# 02_CAN.net
KiCad netlist of a schematic drawn in Altium Designer
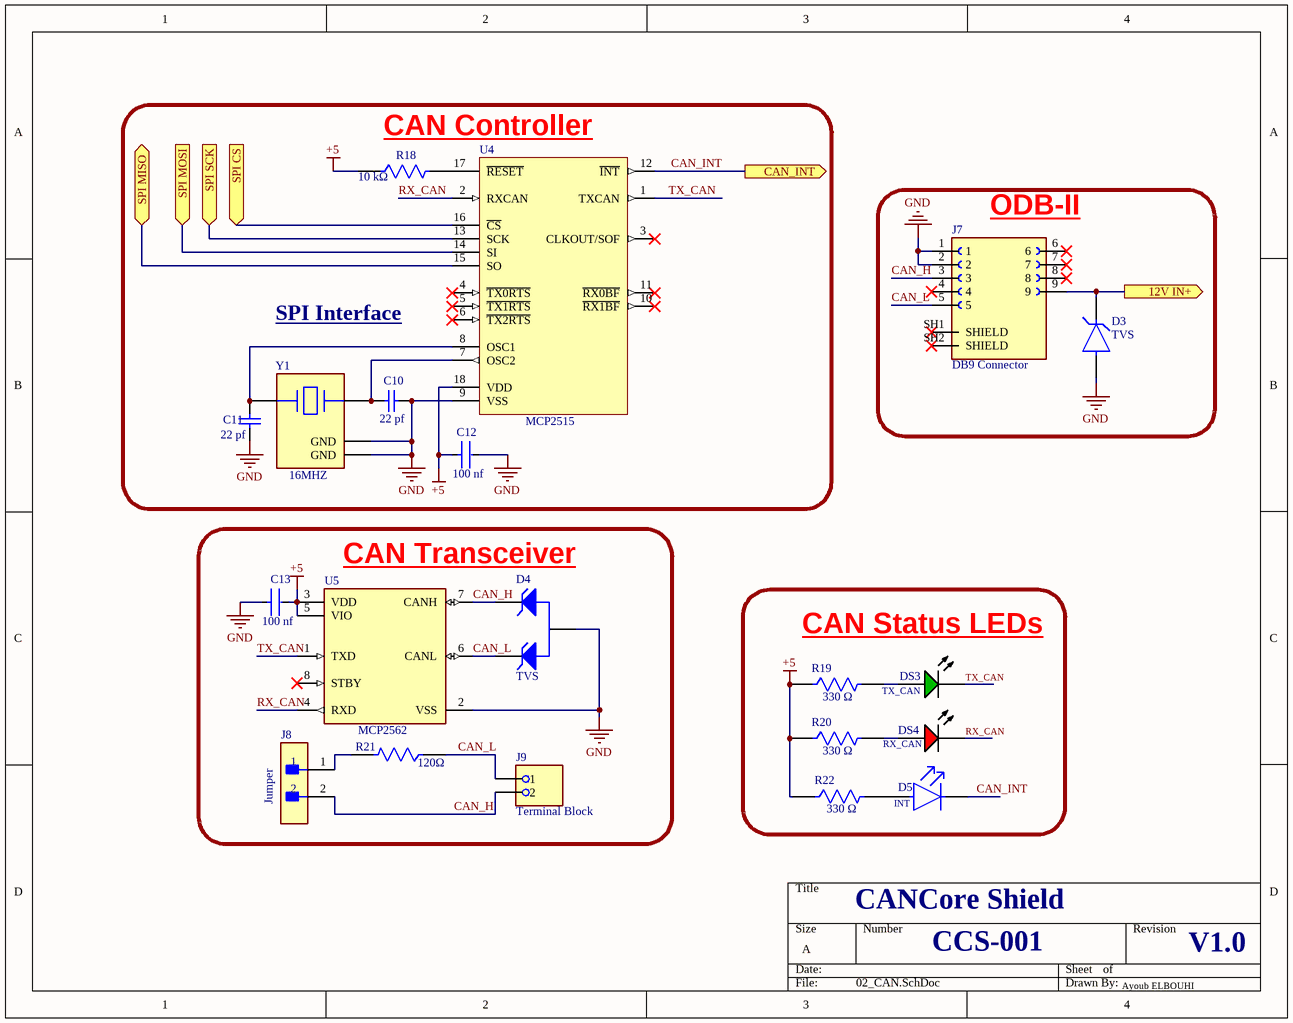
[diagram p0: 02_CAN.SchDoc]

(export (version "E")
  (design (tool "Eeschema 10.0.6"))
  (components
    (comp (ref "C10")
      (value "22 pf")
      (footprint "CAPC1608X90X35ML15T15")
      (fields
        (field (name "MANUFACTURER") "AVX Interconnect / Elco")
        (field (name "PART NUMBER") "06035A220KAT2A")
      )
      (libsource (lib "Altium Content Vault") (part "CAP"))
    )
    (comp (ref "C11")
      (value "22 pf")
      (footprint "CAPC1608X90X35ML15T15")
      (fields
        (field (name "MANUFACTURER") "AVX Interconnect / Elco")
        (field (name "PART NUMBER") "06035A220KAT2A")
      )
      (libsource (lib "Altium Content Vault") (part "CAP"))
    )
    (comp (ref "C12")
      (value "100 nf")
      (footprint "FP-0204-L_0_52_0_05-W_1_0-IPC_B")
      (description "None")
      (fields (field (name "TOLERANCE") "20%"))
      (libsource (lib "Altium Content Vault") (part "b4654b650e69147ec39a6b967a45e02"))
    )
    (comp (ref "C13")
      (value "100 nf")
      (footprint "FP-0204-L_0_52_0_05-W_1_0-IPC_B")
      (description "None")
      (fields (field (name "TOLERANCE") "20%"))
      (libsource (lib "Altium Content Vault") (part "b4654b650e69147ec39a6b967a45e02"))
    )
    (comp (ref "D3")
      (value "TVS")
      (footprint "FP-SMBJ-MFG")
      (description "TVS DIODE 24V 38.9V SMB")
      (libsource (lib "Altium Content Vault") (part "f813f71cba58e380607f5dd3caf9714"))
    )
    (comp (ref "D4")
      (value "TVS")
      (footprint "JSCJ-SOT23-3_V")
      (description "Uni-direction ESD Protection Diode, 5 V, 10 uA, 3-Pin SOT23, RoHS, Tape and Reel")
      (fields (field (name "MANUFACTURER") "Jiangsu Changjiang Electronics Technology"))
      (libsource (lib "Altium Content Vault") (part "DZEN-KKA-3"))
    )
    (comp (ref "D5")
      (value "INT")
      (footprint "FP-LTST-C170TBKT-MFG")
      (description "LED BLUE CLEAR SMD")
      (libsource (lib "Altium Content Vault") (part "8706943c75ba83719d021d2fdc84c58"))
    )
    (comp (ref "DS3")
      (value "TX_CAN")
      (footprint "LTST-LTST-C170KGKT-2_V")
      (description "Ultra Bright AlInGaP Chip LED, 75 mW, -55 to 85 degC, 2-Pin SMD (0805), RoHS, Tape and Reel")
      (fields (field (name "MANUFACTURER") "Lite-On"))
      (libsource (lib "Altium Content Vault") (part "LED-GREEN-KA-2"))
    )
    (comp (ref "DS4")
      (value "RX_CAN")
      (footprint "LTST-C170KRKT_V")
      (description "LED Red, 75 mW, 54 mcd, -55 to 85 degC, 2-Pin SMD, RoHS, Tape and Reel")
      (fields (field (name "MANUFACTURER") "Lite-On"))
      (libsource (lib "Altium Content Vault") (part "LED-RED-AK-2"))
    )
    (comp (ref "J7")
      (value "DB9 Connector")
      (footprint "AMPHENOL_L77SDE09SA4CH4F48")
      (fields
        (field (name "MF") "Amphenol ICC (Commercial Products)")
        (field (name "MP") "L77SDE09SA4CH4F48")
      )
      (libsource (lib "L77SDE09SA4CH4F48") (part "L77SDE09SA4CH4F48"))
    )
    (comp (ref "J8")
      (value "Jumper")
      (footprint "FP-TSW-102-07-G-S-MFG")
      (description "CONN HEADER VERT 2POS 2.54MM")
      (fields
        (field (name "MANUFACTURER") "Samtec")
        (field (name "MANUFACTURER PART NUMBER") "TSW-102-07-G-S")
      )
      (libsource (lib "Altium Content Vault") (part "3bc925449376181038e59eaffc5286c"))
    )
    (comp (ref "J9")
      (value "Terminal Block")
      (footprint "PHOENIX_1935161")
      (description "PCB Terminal Screw 5mm 16AWG 400V 17.5A 2 Position COMBICON PT Series ¦ Phoenix Contact 1935161")
      (fields (field (name "MF") "Phoenix Contact") (field (name "MP") "1935161"))
      (libsource (lib "1935161") (part "1935161"))
    )
    (comp (ref "R18")
      (value "10 kΩ")
      (footprint "FP-RC0603-0_55-IPC_C")
      (description "RES 10K OHM 1% 1/10W 0603")
      (fields (field (name "TOLERANCE") "1%"))
      (libsource (lib "Altium Content Vault") (part "1029c3af85768c4190bb7ad29bc67b5"))
    )
    (comp (ref "R19")
      (value "330 Ω")
      (footprint "FP-RT0603-MFG")
      (description "RES SMD 330 OHM 1% 1/10W 0603")
      (fields
        (field (name "TOLERANCE") "0.01")
        (field (name "OCTOPART") "https://octopart.com/rt0603frd07330rl-yageo-71395358")
      )
      (libsource (lib "Altium Content Vault") (part "1029c3af85768c4190bb7ad29bc67b5"))
    )
    (comp (ref "R20")
      (value "330 Ω")
      (footprint "FP-RT0603-MFG")
      (description "RES SMD 330 OHM 1% 1/10W 0603")
      (fields
        (field (name "TOLERANCE") "0.01")
        (field (name "OCTOPART") "https://octopart.com/rt0603frd07330rl-yageo-71395358")
      )
      (libsource (lib "Altium Content Vault") (part "1029c3af85768c4190bb7ad29bc67b5"))
    )
    (comp (ref "R21")
      (value "120Ω")
      (footprint "FP-AT0603-IPC_A")
      (description "Thin Film Chip Resistors Automotive Grade 120Ω 1% 50ppm/°C 0603")
      (libsource (lib "Altium Content Vault") (part "1029c3af85768c4190bb7ad29bc67b5"))
    )
    (comp (ref "R22")
      (value "330 Ω")
      (footprint "FP-RT0603-MFG")
      (description "RES SMD 330 OHM 1% 1/10W 0603")
      (fields
        (field (name "TOLERANCE") "0.01")
        (field (name "OCTOPART") "https://octopart.com/rt0603frd07330rl-yageo-71395358")
      )
      (libsource (lib "Altium Content Vault") (part "1029c3af85768c4190bb7ad29bc67b5"))
    )
    (comp (ref "U4")
      (value "MCP2515")
      (footprint "SOIC-SO18_N")
      (description "Stand-Alone CAN Controller With SPI Interface, 18-Pin SOIC, Extended Temperature, Tape and Reel")
      (libsource (lib "Altium Content Vault") (part "COM-CAN-MCP2515-18"))
    )
    (comp (ref "U5")
      (value "MCP2562")
      (footprint "FP-C04-057-SN-IPC_B")
      (description "IC TRANSCEIVER 1/1 8SOIC")
      (libsource (lib "Altium Content Vault") (part "fcb6c66e4429206983adab9201371df"))
    )
    (comp (ref "Y1")
      (value "16MHZ")
      (footprint "FP-ABM8G-MFG")
      (description "Crystal 16MHz ±20ppm (Tol) ±30ppm (Stability) 18pF FUND 80Ω 4-Pin SMD T/R")
      (fields (field (name "TOLERANCE") "20ppm"))
      (libsource (lib "Altium Content Vault") (part "48e526d86b7f2615d98721063c72f49"))
    )
  )
  (nets
    (net (code "1") (name "+5") (class "Default")
      (node (ref "C12") (pin "1") (pinfunction "1_1") (pintype "passive"))
      (node (ref "C13") (pin "2") (pinfunction "2_2") (pintype "passive"))
      (node (ref "R18") (pin "1") (pinfunction "1_1") (pintype "passive"))
      (node (ref "R19") (pin "1") (pinfunction "1_1") (pintype "passive"))
      (node (ref "R20") (pin "1") (pinfunction "1_1") (pintype "passive"))
      (node (ref "R22") (pin "1") (pinfunction "1_1") (pintype "passive"))
      (node (ref "U4") (pin "18") (pinfunction "VDD_18") (pintype "power_in"))
      (node (ref "U5") (pin "3") (pinfunction "VDD_3") (pintype "power_in"))
      (node (ref "U5") (pin "5") (pinfunction "VIO_5") (pintype "power_in"))
    )
    (net (code "2") (name "/12V IN+") (class "Default")
      (node (ref "D3") (pin "1") (pinfunction "C_1") (pintype "passive"))
      (node (ref "J7") (pin "9") (pinfunction "9_9") (pintype "passive"))
    )
    (net (code "3") (name "/CAN_H") (class "Default")
      (node (ref "D4") (pin "1") (pinfunction "K_1") (pintype "passive"))
      (node (ref "J7") (pin "3") (pinfunction "3_3") (pintype "passive"))
      (node (ref "J8") (pin "2") (pinfunction "2_2") (pintype "passive"))
      (node (ref "J9") (pin "2") (pinfunction "2_2") (pintype "passive"))
      (node (ref "U5") (pin "7") (pinfunction "CANH_7") (pintype "bidirectional"))
    )
    (net (code "4") (name "/CAN_INT") (class "Default")
      (node (ref "D5") (pin "1") (pinfunction "C_1") (pintype "passive"))
      (node (ref "U4") (pin "12") (pinfunction "~{INT}_12") (pintype "output"))
    )
    (net (code "5") (name "/CAN_L") (class "Default")
      (node (ref "D4") (pin "2") (pinfunction "K_2") (pintype "passive"))
      (node (ref "J7") (pin "5") (pinfunction "5_5") (pintype "passive"))
      (node (ref "J9") (pin "1") (pinfunction "1_1") (pintype "passive"))
      (node (ref "R21") (pin "1") (pinfunction "1_1") (pintype "passive"))
      (node (ref "U5") (pin "6") (pinfunction "CANL_6") (pintype "bidirectional"))
    )
    (net (code "6") (name "/RX_CAN") (class "Default")
      (node (ref "DS4") (pin "2") (pinfunction "K_2") (pintype "passive"))
      (node (ref "U4") (pin "2") (pinfunction "RXCAN_2") (pintype "input"))
      (node (ref "U5") (pin "4") (pinfunction "RXD_4") (pintype "output"))
    )
    (net (code "7") (name "/SPI CS") (class "Default")
      (node (ref "U4") (pin "16") (pinfunction "~{CS}_16") (pintype "passive"))
    )
    (net (code "8") (name "/SPI MISO") (class "Default")
      (node (ref "U4") (pin "15") (pinfunction "SO_15") (pintype "passive"))
    )
    (net (code "9") (name "/SPI MOSI") (class "Default")
      (node (ref "U4") (pin "14") (pinfunction "SI_14") (pintype "passive"))
    )
    (net (code "10") (name "/SPI SCK") (class "Default")
      (node (ref "U4") (pin "13") (pinfunction "SCK_13") (pintype "passive"))
    )
    (net (code "11") (name "/TX_CAN") (class "Default")
      (node (ref "DS3") (pin "1") (pinfunction "K_1") (pintype "passive"))
      (node (ref "U4") (pin "1") (pinfunction "TXCAN_1") (pintype "output"))
      (node (ref "U5") (pin "1") (pinfunction "TXD_1") (pintype "input"))
    )
    (net (code "12") (name "GND") (class "Default")
      (node (ref "C10") (pin "1") (pinfunction "1_1") (pintype "passive"))
      (node (ref "C11") (pin "2") (pinfunction "2_2") (pintype "passive"))
      (node (ref "C12") (pin "2") (pinfunction "2_2") (pintype "passive"))
      (node (ref "C13") (pin "1") (pinfunction "1_1") (pintype "passive"))
      (node (ref "D3") (pin "2") (pinfunction "A_2") (pintype "passive"))
      (node (ref "D4") (pin "3") (pinfunction "A_3") (pintype "passive"))
      (node (ref "J7") (pin "1") (pinfunction "1_1") (pintype "passive"))
      (node (ref "J7") (pin "2") (pinfunction "2_2") (pintype "passive"))
      (node (ref "U4") (pin "9") (pinfunction "VSS_9") (pintype "power_in"))
      (node (ref "U5") (pin "2") (pinfunction "VSS_2") (pintype "power_in"))
      (node (ref "Y1") (pin "2") (pinfunction "GND_2") (pintype "power_in"))
      (node (ref "Y1") (pin "4") (pinfunction "GND_4") (pintype "power_in"))
    )
    (net (code "13") (name "Net-(D5-A)") (class "Default")
      (node (ref "D5") (pin "2") (pinfunction "A_2") (pintype "passive"))
      (node (ref "R22") (pin "2") (pinfunction "2_2") (pintype "passive"))
    )
    (net (code "14") (name "Net-(DS3-A)") (class "Default")
      (node (ref "DS3") (pin "2") (pinfunction "A_2") (pintype "passive"))
      (node (ref "R19") (pin "2") (pinfunction "2_2") (pintype "passive"))
    )
    (net (code "15") (name "Net-(DS4-A)") (class "Default")
      (node (ref "DS4") (pin "1") (pinfunction "A_1") (pintype "passive"))
      (node (ref "R20") (pin "2") (pinfunction "2_2") (pintype "passive"))
    )
    (net (code "16") (name "Net-(J8-Pad1)") (class "Default")
      (node (ref "J8") (pin "1") (pinfunction "1_1") (pintype "passive"))
      (node (ref "R21") (pin "2") (pinfunction "2_2") (pintype "passive"))
    )
    (net (code "17") (name "Net-(U4-OSC1)") (class "Default")
      (node (ref "C11") (pin "1") (pinfunction "1_1") (pintype "passive"))
      (node (ref "U4") (pin "8") (pinfunction "OSC1_8") (pintype "passive"))
      (node (ref "Y1") (pin "1") (pinfunction "1_1") (pintype "passive"))
    )
    (net (code "18") (name "Net-(U4-OSC2)") (class "Default")
      (node (ref "C10") (pin "2") (pinfunction "2_2") (pintype "passive"))
      (node (ref "U4") (pin "7") (pinfunction "OSC2_7") (pintype "output"))
      (node (ref "Y1") (pin "3") (pinfunction "3_3") (pintype "passive"))
    )
    (net (code "19") (name "Net-(U4-~{RESET})") (class "Default")
      (node (ref "R18") (pin "2") (pinfunction "2_2") (pintype "passive"))
      (node (ref "U4") (pin "17") (pinfunction "~{RESET}_17") (pintype "passive"))
    )
    (net (code "20") (name "unconnected-(J7-Pad4)") (class "Default")
      (node (ref "J7") (pin "4") (pinfunction "4_4") (pintype "passive+no_connect"))
    )
    (net (code "21") (name "unconnected-(J7-Pad6)") (class "Default")
      (node (ref "J7") (pin "6") (pinfunction "6_6") (pintype "passive+no_connect"))
    )
    (net (code "22") (name "unconnected-(J7-Pad7)") (class "Default")
      (node (ref "J7") (pin "7") (pinfunction "7_7") (pintype "passive+no_connect"))
    )
    (net (code "23") (name "unconnected-(J7-Pad8)") (class "Default")
      (node (ref "J7") (pin "8") (pinfunction "8_8") (pintype "passive+no_connect"))
    )
    (net (code "24") (name "unconnected-(J7-SHIELD-PadSH1)") (class "Default")
      (node (ref "J7") (pin "SH1") (pinfunction "SHIELD_SH1") (pintype "passive+no_connect"))
    )
    (net (code "25") (name "unconnected-(J7-SHIELD-PadSH2)") (class "Default")
      (node (ref "J7") (pin "SH2") (pinfunction "SHIELD_SH2") (pintype "passive+no_connect"))
    )
    (net (code "26") (name "unconnected-(U4-CLKOUT{slash}SOF-Pad3)") (class "Default")
      (node (ref "U4") (pin "3") (pinfunction "CLKOUT/SOF_3") (pintype "output+no_connect"))
    )
    (net (code "27") (name "unconnected-(U4-~{RX0BF}-Pad11)") (class "Default")
      (node (ref "U4") (pin "11") (pinfunction "~{RX0BF}_11") (pintype "output+no_connect"))
    )
    (net (code "28") (name "unconnected-(U4-~{RX1BF}-Pad10)") (class "Default")
      (node (ref "U4") (pin "10") (pinfunction "~{RX1BF}_10") (pintype "output+no_connect"))
    )
    (net (code "29") (name "unconnected-(U4-~{TX0RTS}-Pad4)") (class "Default")
      (node (ref "U4") (pin "4") (pinfunction "~{TX0RTS}_4") (pintype "input+no_connect"))
    )
    (net (code "30") (name "unconnected-(U4-~{TX1RTS}-Pad5)") (class "Default")
      (node (ref "U4") (pin "5") (pinfunction "~{TX1RTS}_5") (pintype "input+no_connect"))
    )
    (net (code "31") (name "unconnected-(U4-~{TX2RTS}-Pad6)") (class "Default")
      (node (ref "U4") (pin "6") (pinfunction "~{TX2RTS}_6") (pintype "input+no_connect"))
    )
    (net (code "32") (name "unconnected-(U5-STBY-Pad8)") (class "Default")
      (node (ref "U5") (pin "8") (pinfunction "STBY_8") (pintype "input+no_connect"))
    )
  )
)
